# tinyLarson.net
KiCad netlist of a schematic drawn in EAGLE
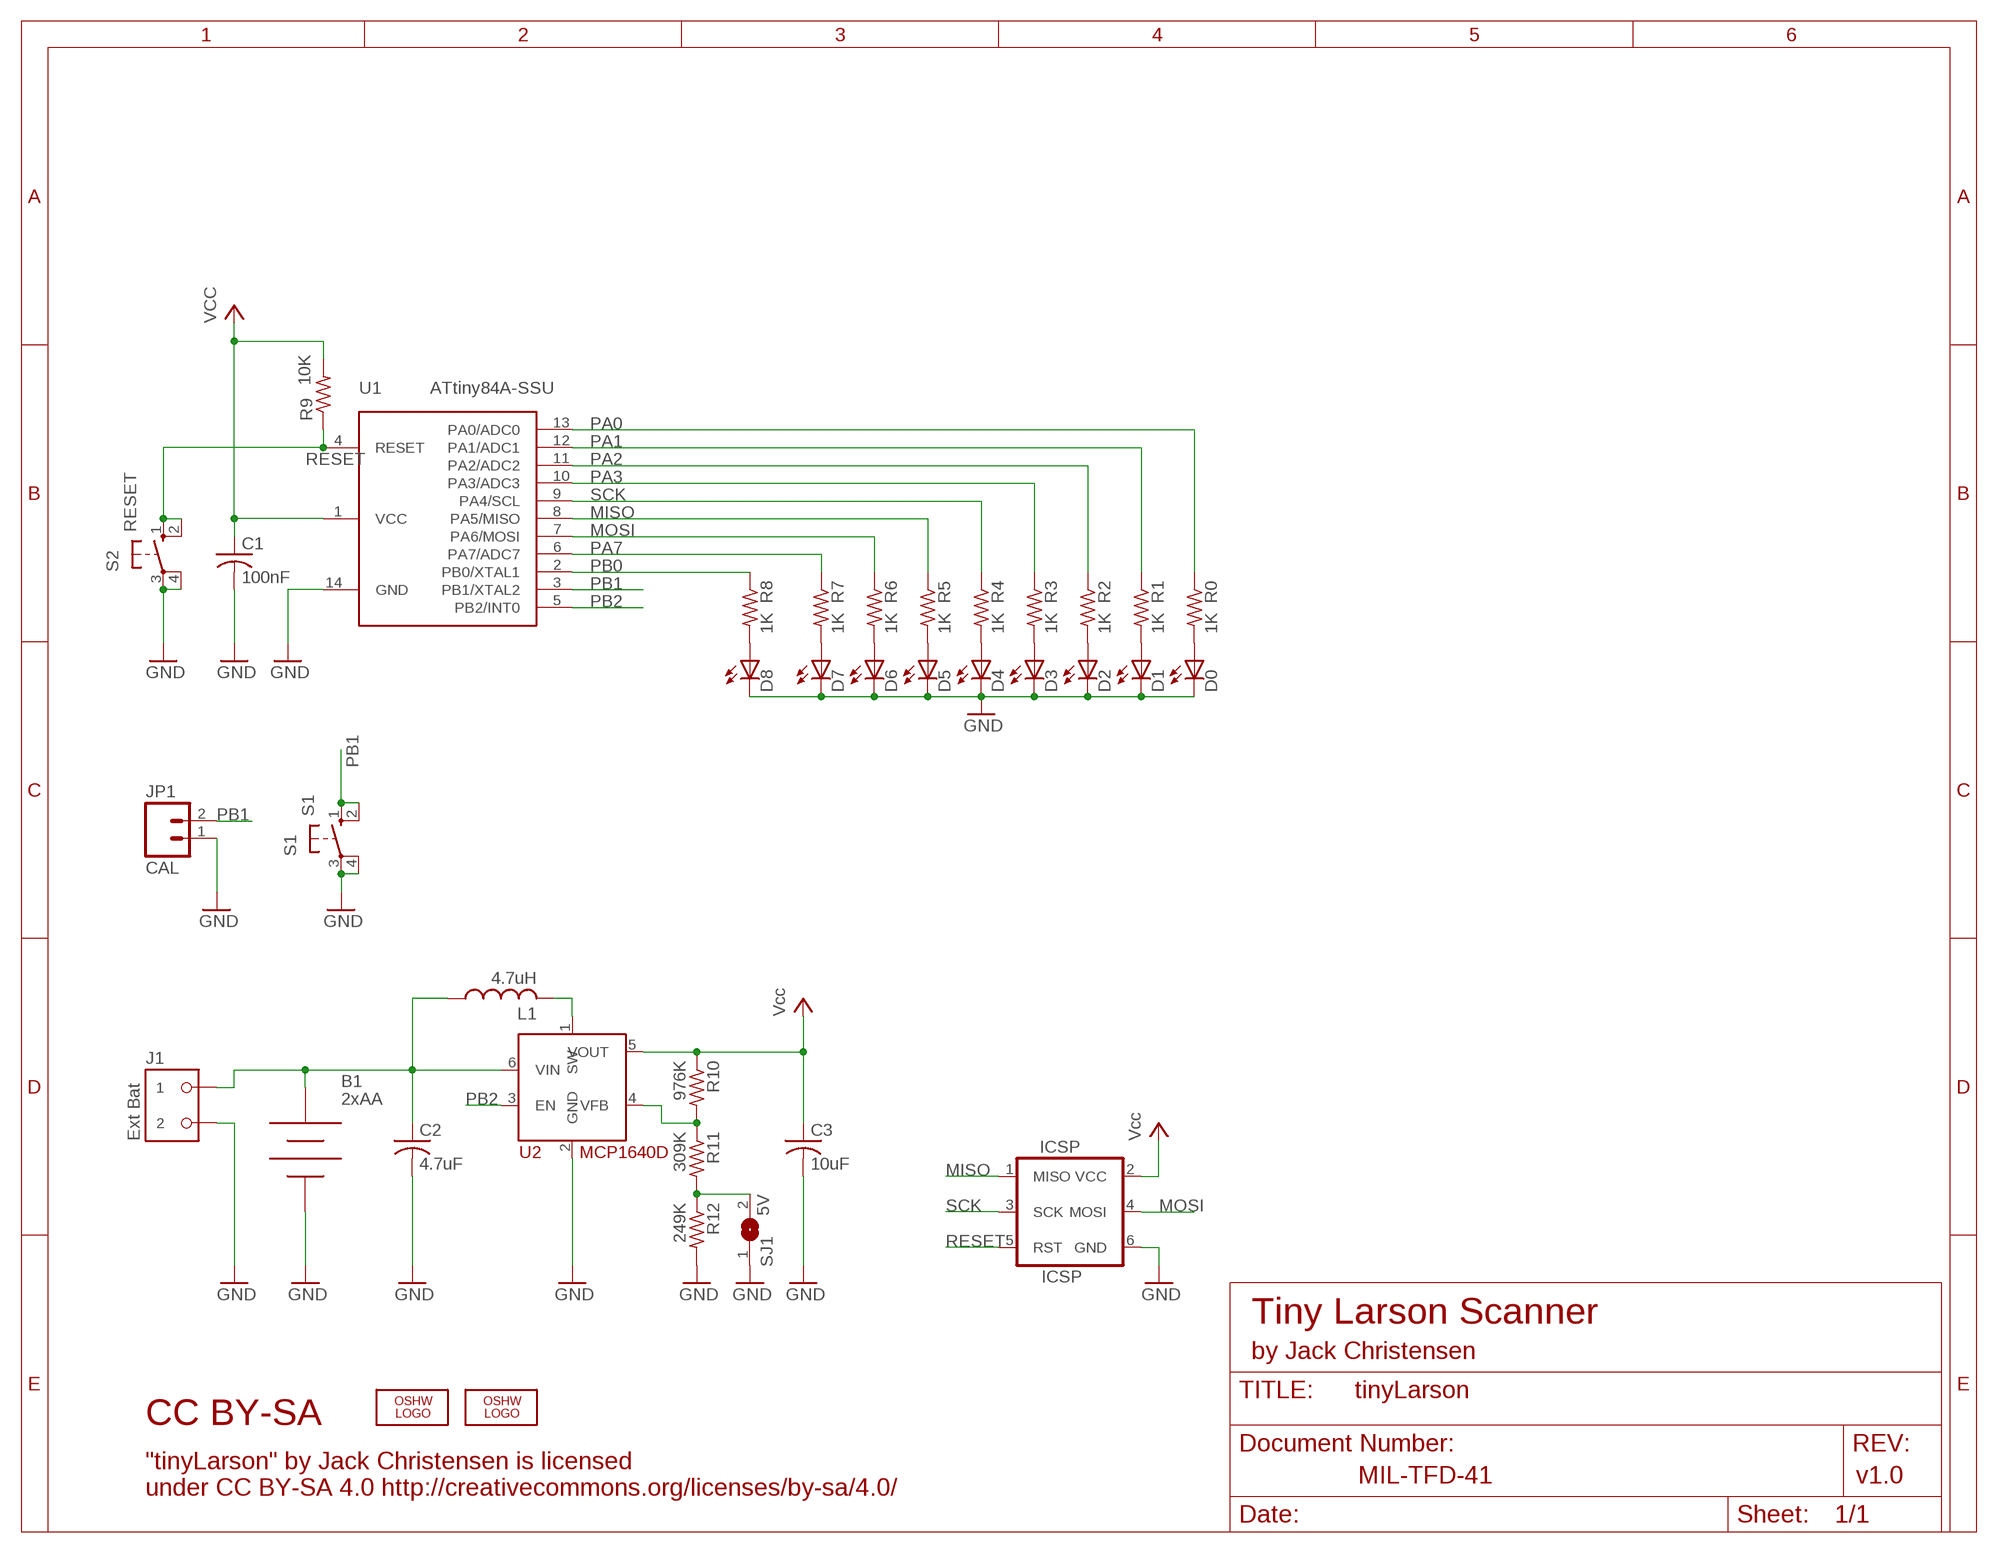
[diagram p0: schematic, sheet 1]

(export (version "E")
  (design (tool "Eeschema 10.0.6"))
  (components
    (comp (ref "B1")
      (value "2xAA")
      (footprint "eagle-import:EAGLE-12BH321P-GR")
      (fields (field (name "MFR") "Keystone"))
      (libsource (lib "eagle-import") (part "BATTERY-2AAEAGLE"))
    )
    (comp (ref "C1")
      (value "100nF")
      (footprint "eagle-import:M0805")
      (libsource (lib "eagle-import") (part "C-USM0805"))
    )
    (comp (ref "C2")
      (value "4.7uF")
      (footprint "eagle-import:M0805")
      (libsource (lib "eagle-import") (part "C-USM0805"))
    )
    (comp (ref "C3")
      (value "10uF")
      (footprint "eagle-import:M0805")
      (libsource (lib "eagle-import") (part "C-USM0805"))
    )
    (comp (ref "D0")
      (value "Yel")
      (footprint "eagle-import:D0805A")
      (fields (field (name "MFR") "Lite-On"))
      (libsource (lib "eagle-import") (part "LEDD0805A"))
    )
    (comp (ref "D1")
      (value "Yel")
      (footprint "eagle-import:D0805A")
      (fields (field (name "MFR") "Lite-On"))
      (libsource (lib "eagle-import") (part "LEDD0805A"))
    )
    (comp (ref "D2")
      (value "Yel")
      (footprint "eagle-import:D0805A")
      (fields (field (name "MFR") "Lite-On"))
      (libsource (lib "eagle-import") (part "LEDD0805A"))
    )
    (comp (ref "D3")
      (value "Yel")
      (footprint "eagle-import:D0805A")
      (fields (field (name "MFR") "Lite-On"))
      (libsource (lib "eagle-import") (part "LEDD0805A"))
    )
    (comp (ref "D4")
      (value "Yel")
      (footprint "eagle-import:D0805A")
      (fields (field (name "MFR") "Lite-On"))
      (libsource (lib "eagle-import") (part "LEDD0805A"))
    )
    (comp (ref "D5")
      (value "Yel")
      (footprint "eagle-import:D0805A")
      (fields (field (name "MFR") "Lite-On"))
      (libsource (lib "eagle-import") (part "LEDD0805A"))
    )
    (comp (ref "D6")
      (value "Yel")
      (footprint "eagle-import:D0805A")
      (fields (field (name "MFR") "Lite-On"))
      (libsource (lib "eagle-import") (part "LEDD0805A"))
    )
    (comp (ref "D7")
      (value "Yel")
      (footprint "eagle-import:D0805")
      (fields (field (name "MFR") "Lite-On"))
      (libsource (lib "eagle-import") (part "LEDD0805"))
    )
    (comp (ref "D8")
      (value "Red")
      (footprint "eagle-import:D0805")
      (fields (field (name "MFR") "Lite-On"))
      (libsource (lib "eagle-import") (part "LEDD0805"))
    )
    (comp (ref "ICSP")
      (value "ICSP")
      (footprint "eagle-import:2X3_LOCK")
      (libsource (lib "eagle-import") (part "AVR_SPI_PRG_62X3_LOCK"))
    )
    (comp (ref "J1")
      (value "Ext Bat")
      (footprint "eagle-import:OST-TB-2-3.5MM")
      (libsource (lib "eagle-import") (part "OST-TB-23.5MM"))
    )
    (comp (ref "JP1")
      (value "CAL")
      (footprint "eagle-import:1X02_LOCK")
      (libsource (lib "eagle-import") (part "M02LOCK"))
    )
    (comp (ref "L1")
      (value "4.7uH")
      (footprint "eagle-import:C1210K")
      (fields (field (name "MFR") "Taiyo Yuden"))
      (libsource (lib "eagle-import") (part "INDUCTORC1210K"))
    )
    (comp (ref "LOGO1")
      (value "OSHW_LOGO_8MILX0100-NT")
      (footprint "eagle-import:OSHW_8X100_NOTEXT")
      (libsource (lib "eagle-import") (part "OSHW_LOGO_8MILX0100-NT"))
    )
    (comp (ref "LOGO2")
      (value "OSHW_LOGO_8MILX0100-NT")
      (footprint "eagle-import:OSHW_8X100_NOTEXT")
      (libsource (lib "eagle-import") (part "OSHW_LOGO_8MILX0100-NT"))
    )
    (comp (ref "R0")
      (value "1K")
      (footprint "eagle-import:M0805")
      (libsource (lib "eagle-import") (part "R-US_M0805"))
    )
    (comp (ref "R1")
      (value "1K")
      (footprint "eagle-import:M0805")
      (libsource (lib "eagle-import") (part "R-US_M0805"))
    )
    (comp (ref "R2")
      (value "1K")
      (footprint "eagle-import:M0805")
      (libsource (lib "eagle-import") (part "R-US_M0805"))
    )
    (comp (ref "R3")
      (value "1K")
      (footprint "eagle-import:M0805")
      (libsource (lib "eagle-import") (part "R-US_M0805"))
    )
    (comp (ref "R4")
      (value "1K")
      (footprint "eagle-import:M0805")
      (libsource (lib "eagle-import") (part "R-US_M0805"))
    )
    (comp (ref "R5")
      (value "1K")
      (footprint "eagle-import:M0805")
      (libsource (lib "eagle-import") (part "R-US_M0805"))
    )
    (comp (ref "R6")
      (value "1K")
      (footprint "eagle-import:M0805")
      (libsource (lib "eagle-import") (part "R-US_M0805"))
    )
    (comp (ref "R7")
      (value "1K")
      (footprint "eagle-import:M0805")
      (libsource (lib "eagle-import") (part "R-US_M0805"))
    )
    (comp (ref "R8")
      (value "1K")
      (footprint "eagle-import:M0805")
      (libsource (lib "eagle-import") (part "R-US_M0805"))
    )
    (comp (ref "R9")
      (value "10K")
      (footprint "eagle-import:M0805")
      (libsource (lib "eagle-import") (part "R-US_M0805"))
    )
    (comp (ref "R10")
      (value "976K")
      (footprint "eagle-import:M0805")
      (libsource (lib "eagle-import") (part "R-US_M0805"))
    )
    (comp (ref "R11")
      (value "309K")
      (footprint "eagle-import:M0805")
      (libsource (lib "eagle-import") (part "R-US_M0805"))
    )
    (comp (ref "R12")
      (value "249K")
      (footprint "eagle-import:M0805")
      (libsource (lib "eagle-import") (part "R-US_M0805"))
    )
    (comp (ref "S1")
      (value "S1")
      (footprint "eagle-import:B3F-10XXOCT")
      (fields (field (name "MFR") "Omron"))
      (libsource (lib "eagle-import") (part "10-XXOCT"))
    )
    (comp (ref "S2")
      (value "RESET")
      (footprint "eagle-import:B3F-10XXOCT")
      (fields (field (name "MFR") "Omron"))
      (libsource (lib "eagle-import") (part "10-XXOCT"))
    )
    (comp (ref "SJ1") (value "5V") (footprint "eagle-import:SJ") (libsource (lib "eagle-import") (part "SJ")))
    (comp (ref "U1")
      (value "ATtiny84A-SSU")
      (footprint "eagle-import:SO14")
      (libsource (lib "eagle-import") (part "ATTINYX4SO14"))
    )
    (comp (ref "U2")
      (value "MCP1640D")
      (footprint "eagle-import:SOT23-6")
      (libsource (lib "eagle-import") (part "MCP1640"))
    )
  )
  (nets
    (net (code "1") (name "/MISO") (class "Default")
      (node (ref "ICSP") (pin "1") (pinfunction "MISO_1") (pintype "passive"))
      (node (ref "R5") (pin "1") (pinfunction "1_1") (pintype "passive"))
      (node (ref "U1") (pin "8") (pinfunction "PA5/MISO_8") (pintype "bidirectional"))
    )
    (net (code "2") (name "/MOSI") (class "Default")
      (node (ref "ICSP") (pin "4") (pinfunction "MOSI_4") (pintype "passive"))
      (node (ref "R6") (pin "1") (pinfunction "1_1") (pintype "passive"))
      (node (ref "U1") (pin "7") (pinfunction "PA6/MOSI_7") (pintype "bidirectional"))
    )
    (net (code "3") (name "/PA0") (class "Default")
      (node (ref "R0") (pin "1") (pinfunction "1_1") (pintype "passive"))
      (node (ref "U1") (pin "13") (pinfunction "PA0/ADC0_13") (pintype "bidirectional"))
    )
    (net (code "4") (name "/PA1") (class "Default")
      (node (ref "R1") (pin "1") (pinfunction "1_1") (pintype "passive"))
      (node (ref "U1") (pin "12") (pinfunction "PA1/ADC1_12") (pintype "bidirectional"))
    )
    (net (code "5") (name "/PA2") (class "Default")
      (node (ref "R2") (pin "1") (pinfunction "1_1") (pintype "passive"))
      (node (ref "U1") (pin "11") (pinfunction "PA2/ADC2_11") (pintype "bidirectional"))
    )
    (net (code "6") (name "/PA3") (class "Default")
      (node (ref "R3") (pin "1") (pinfunction "1_1") (pintype "passive"))
      (node (ref "U1") (pin "10") (pinfunction "PA3/ADC3_10") (pintype "bidirectional"))
    )
    (net (code "7") (name "/PA7") (class "Default")
      (node (ref "R7") (pin "1") (pinfunction "1_1") (pintype "passive"))
      (node (ref "U1") (pin "6") (pinfunction "PA7/ADC7_6") (pintype "bidirectional"))
    )
    (net (code "8") (name "/PB0") (class "Default")
      (node (ref "R8") (pin "1") (pinfunction "1_1") (pintype "passive"))
      (node (ref "U1") (pin "2") (pinfunction "PB0/XTAL1_2") (pintype "bidirectional"))
    )
    (net (code "9") (name "/PB1") (class "Default")
      (node (ref "JP1") (pin "2") (pinfunction "2_2") (pintype "passive"))
      (node (ref "S1") (pin "1") (pinfunction "S_1") (pintype "passive"))
      (node (ref "S1") (pin "2") (pinfunction "S1_2") (pintype "passive"))
      (node (ref "U1") (pin "3") (pinfunction "PB1/XTAL2_3") (pintype "bidirectional"))
    )
    (net (code "10") (name "/PB2") (class "Default")
      (node (ref "U1") (pin "5") (pinfunction "PB2/INT0_5") (pintype "bidirectional"))
      (node (ref "U2") (pin "3") (pinfunction "EN_3") (pintype "passive"))
    )
    (net (code "11") (name "/RESET") (class "Default")
      (node (ref "ICSP") (pin "5") (pinfunction "RST_5") (pintype "passive"))
      (node (ref "R9") (pin "1") (pinfunction "1_1") (pintype "passive"))
      (node (ref "S2") (pin "1") (pinfunction "S_1") (pintype "passive"))
      (node (ref "S2") (pin "2") (pinfunction "S1_2") (pintype "passive"))
      (node (ref "U1") (pin "4") (pinfunction "RESET_4") (pintype "bidirectional"))
    )
    (net (code "12") (name "/SCK") (class "Default")
      (node (ref "ICSP") (pin "3") (pinfunction "SCK_3") (pintype "passive"))
      (node (ref "R4") (pin "1") (pinfunction "1_1") (pintype "passive"))
      (node (ref "U1") (pin "9") (pinfunction "PA4/SCL_9") (pintype "bidirectional"))
    )
    (net (code "13") (name "GND") (class "Default")
      (node (ref "B1") (pin "NEG") (pinfunction "NEG_NEG") (pintype "bidirectional"))
      (node (ref "C1") (pin "2") (pinfunction "2_2") (pintype "passive"))
      (node (ref "C2") (pin "2") (pinfunction "2_2") (pintype "passive"))
      (node (ref "C3") (pin "2") (pinfunction "2_2") (pintype "passive"))
      (node (ref "D0") (pin "K") (pinfunction "C_K") (pintype "passive"))
      (node (ref "D1") (pin "K") (pinfunction "C_K") (pintype "passive"))
      (node (ref "D2") (pin "K") (pinfunction "C_K") (pintype "passive"))
      (node (ref "D3") (pin "K") (pinfunction "C_K") (pintype "passive"))
      (node (ref "D4") (pin "K") (pinfunction "C_K") (pintype "passive"))
      (node (ref "D5") (pin "K") (pinfunction "C_K") (pintype "passive"))
      (node (ref "D6") (pin "K") (pinfunction "C_K") (pintype "passive"))
      (node (ref "D7") (pin "K") (pinfunction "C_K") (pintype "passive"))
      (node (ref "D8") (pin "K") (pinfunction "C_K") (pintype "passive"))
      (node (ref "ICSP") (pin "6") (pinfunction "GND_6") (pintype "passive"))
      (node (ref "J1") (pin "P$2") (pinfunction "2_P$2") (pintype "passive"))
      (node (ref "JP1") (pin "1") (pinfunction "1_1") (pintype "passive"))
      (node (ref "R12") (pin "2") (pinfunction "2_2") (pintype "passive"))
      (node (ref "S1") (pin "3") (pinfunction "P_3") (pintype "passive"))
      (node (ref "S1") (pin "4") (pinfunction "P1_4") (pintype "passive"))
      (node (ref "S2") (pin "3") (pinfunction "P_3") (pintype "passive"))
      (node (ref "S2") (pin "4") (pinfunction "P1_4") (pintype "passive"))
      (node (ref "SJ1") (pin "1") (pinfunction "1_1") (pintype "passive"))
      (node (ref "U1") (pin "14") (pinfunction "GND_14") (pintype "bidirectional"))
      (node (ref "U2") (pin "2") (pinfunction "GND_2") (pintype "passive"))
    )
    (net (code "14") (name "Net-(D0-PadA)") (class "Default")
      (node (ref "D0") (pin "A") (pinfunction "A_A") (pintype "passive"))
      (node (ref "R0") (pin "2") (pinfunction "2_2") (pintype "passive"))
    )
    (net (code "15") (name "Net-(D1-PadA)") (class "Default")
      (node (ref "D1") (pin "A") (pinfunction "A_A") (pintype "passive"))
      (node (ref "R1") (pin "2") (pinfunction "2_2") (pintype "passive"))
    )
    (net (code "16") (name "Net-(D2-PadA)") (class "Default")
      (node (ref "D2") (pin "A") (pinfunction "A_A") (pintype "passive"))
      (node (ref "R2") (pin "2") (pinfunction "2_2") (pintype "passive"))
    )
    (net (code "17") (name "Net-(D3-PadA)") (class "Default")
      (node (ref "D3") (pin "A") (pinfunction "A_A") (pintype "passive"))
      (node (ref "R3") (pin "2") (pinfunction "2_2") (pintype "passive"))
    )
    (net (code "18") (name "Net-(D4-PadA)") (class "Default")
      (node (ref "D4") (pin "A") (pinfunction "A_A") (pintype "passive"))
      (node (ref "R4") (pin "2") (pinfunction "2_2") (pintype "passive"))
    )
    (net (code "19") (name "Net-(D5-PadA)") (class "Default")
      (node (ref "D5") (pin "A") (pinfunction "A_A") (pintype "passive"))
      (node (ref "R5") (pin "2") (pinfunction "2_2") (pintype "passive"))
    )
    (net (code "20") (name "Net-(D6-PadA)") (class "Default")
      (node (ref "D6") (pin "A") (pinfunction "A_A") (pintype "passive"))
      (node (ref "R6") (pin "2") (pinfunction "2_2") (pintype "passive"))
    )
    (net (code "21") (name "Net-(D7-PadA)") (class "Default")
      (node (ref "D7") (pin "A") (pinfunction "A_A") (pintype "passive"))
      (node (ref "R7") (pin "2") (pinfunction "2_2") (pintype "passive"))
    )
    (net (code "22") (name "Net-(D8-PadA)") (class "Default")
      (node (ref "D8") (pin "A") (pinfunction "A_A") (pintype "passive"))
      (node (ref "R8") (pin "2") (pinfunction "2_2") (pintype "passive"))
    )
    (net (code "23") (name "Net-(J1-1)") (class "Default")
      (node (ref "B1") (pin "POS") (pinfunction "POS_POS") (pintype "bidirectional"))
      (node (ref "C2") (pin "1") (pinfunction "1_1") (pintype "passive"))
      (node (ref "J1") (pin "P$1") (pinfunction "1_P$1") (pintype "passive"))
      (node (ref "L1") (pin "1") (pinfunction "1_1") (pintype "passive"))
      (node (ref "U2") (pin "6") (pinfunction "VIN_6") (pintype "passive"))
    )
    (net (code "24") (name "Net-(R11-Pad2)") (class "Default")
      (node (ref "R11") (pin "2") (pinfunction "2_2") (pintype "passive"))
      (node (ref "R12") (pin "1") (pinfunction "1_1") (pintype "passive"))
      (node (ref "SJ1") (pin "2") (pinfunction "2_2") (pintype "passive"))
    )
    (net (code "25") (name "Net-(U2-SW)") (class "Default")
      (node (ref "L1") (pin "2") (pinfunction "2_2") (pintype "passive"))
      (node (ref "U2") (pin "1") (pinfunction "SW_1") (pintype "passive"))
    )
    (net (code "26") (name "Net-(U2-VFB)") (class "Default")
      (node (ref "R10") (pin "2") (pinfunction "2_2") (pintype "passive"))
      (node (ref "R11") (pin "1") (pinfunction "1_1") (pintype "passive"))
      (node (ref "U2") (pin "4") (pinfunction "VFB_4") (pintype "passive"))
    )
    (net (code "27") (name "VCC") (class "Default")
      (node (ref "C1") (pin "1") (pinfunction "1_1") (pintype "passive"))
      (node (ref "C3") (pin "1") (pinfunction "1_1") (pintype "passive"))
      (node (ref "ICSP") (pin "2") (pinfunction "VCC_2") (pintype "passive"))
      (node (ref "R10") (pin "1") (pinfunction "1_1") (pintype "passive"))
      (node (ref "R9") (pin "2") (pinfunction "2_2") (pintype "passive"))
      (node (ref "U1") (pin "1") (pinfunction "VCC_1") (pintype "bidirectional"))
      (node (ref "U2") (pin "5") (pinfunction "VOUT_5") (pintype "passive"))
    )
  )
)
